# pr0board_main.net
KiCad netlist of a schematic drawn in EAGLE
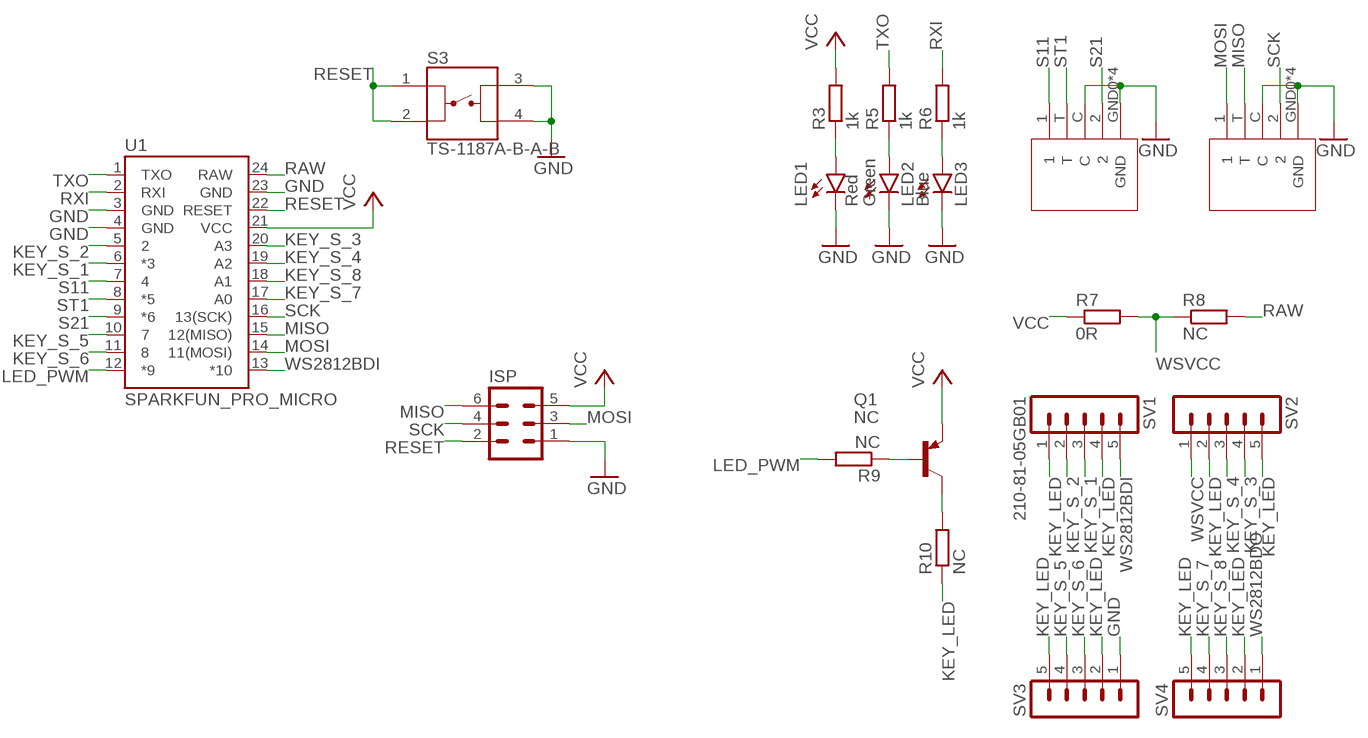
[diagram p0: schematic, sheet 1]

(export (version "E")
  (design (tool "Eeschema 10.0.6"))
  (components
    (comp (ref "ISP")
      (value "MA03-2")
      (footprint "eagle-import:MA03-2")
      (libsource (lib "eagle-import") (part "MA03-2"))
    )
    (comp (ref "LED1")
      (value "Red")
      (footprint "eagle-import:CHIP-LED0603")
      (libsource (lib "eagle-import") (part "LEDCHIP-LED0603"))
    )
    (comp (ref "LED2")
      (value "Green")
      (footprint "eagle-import:CHIP-LED0603")
      (libsource (lib "eagle-import") (part "LEDCHIP-LED0603"))
    )
    (comp (ref "LED3")
      (value "Blue")
      (footprint "eagle-import:CHIP-LED0603")
      (libsource (lib "eagle-import") (part "LEDCHIP-LED0603"))
    )
    (comp (ref "Q1")
      (value "NC")
      (footprint "eagle-import:SOT23")
      (libsource (lib "eagle-import") (part "-?SOT23MMBTA56"))
    )
    (comp (ref "R3")
      (value "1k")
      (footprint "eagle-import:R0603")
      (libsource (lib "eagle-import") (part "resistor_348_R-EU_R0603"))
    )
    (comp (ref "R5")
      (value "1k")
      (footprint "eagle-import:R0603")
      (libsource (lib "eagle-import") (part "resistor_348_R-EU_R0603"))
    )
    (comp (ref "R6")
      (value "1k")
      (footprint "eagle-import:R0603")
      (libsource (lib "eagle-import") (part "resistor_348_R-EU_R0603"))
    )
    (comp (ref "R7")
      (value "0R")
      (footprint "eagle-import:R0603")
      (libsource (lib "eagle-import") (part "resistor_348_R-EU_R0603"))
    )
    (comp (ref "R8")
      (value "NC")
      (footprint "eagle-import:R0603")
      (libsource (lib "eagle-import") (part "resistor_348_R-EU_R0603"))
    )
    (comp (ref "R9")
      (value "NC")
      (footprint "eagle-import:R0603")
      (libsource (lib "eagle-import") (part "R-EU_R0603"))
    )
    (comp (ref "R10")
      (value "NC")
      (footprint "eagle-import:R0805")
      (libsource (lib "eagle-import") (part "R-EU_R0805"))
    )
    (comp (ref "S1")
      (value "TM-2024A")
      (footprint "eagle-import:TM-2024A")
      (libsource (lib "eagle-import") (part "TM-2024A"))
    )
    (comp (ref "S2")
      (value "TM-2024A")
      (footprint "eagle-import:TM-2024A")
      (libsource (lib "eagle-import") (part "TM-2024A"))
    )
    (comp (ref "S3")
      (value "TS-1187A-B-A-B")
      (footprint "eagle-import:SW_PTS525SM15SMTR2LFS")
      (fields (field (name "MF") "C&K") (field (name "MP") "PTS525SM15SMTR2LFS"))
      (libsource (lib "eagle-import") (part "PTS525SM15SMTR2LFS"))
    )
    (comp (ref "SV1")
      (value "210-81-05GB01")
      (footprint "eagle-import:MA05-1")
      (libsource (lib "eagle-import") (part "MA05-1"))
    )
    (comp (ref "SV2")
      (value "MA05-1")
      (footprint "eagle-import:MA05-1")
      (libsource (lib "eagle-import") (part "MA05-1"))
    )
    (comp (ref "SV3")
      (value "MA05-1")
      (footprint "eagle-import:MA05-1")
      (libsource (lib "eagle-import") (part "MA05-1"))
    )
    (comp (ref "SV4")
      (value "MA05-1")
      (footprint "eagle-import:MA05-1")
      (libsource (lib "eagle-import") (part "MA05-1"))
    )
    (comp (ref "U1")
      (value "SPARKFUN_PRO_MICRO")
      (footprint "eagle-import:SPARKFUN_PRO_MICRO")
      (libsource (lib "eagle-import") (part "SPARKFUN_PRO_MICRO"))
    )
  )
  (nets
    (net (code "1") (name "/KEY_LED") (class "Default")
      (node (ref "R10") (pin "1") (pinfunction "1_1") (pintype "passive"))
      (node (ref "SV1") (pin "1") (pinfunction "1_1") (pintype "passive"))
      (node (ref "SV1") (pin "4") (pinfunction "4_4") (pintype "passive"))
      (node (ref "SV2") (pin "2") (pinfunction "2_2") (pintype "passive"))
      (node (ref "SV2") (pin "5") (pinfunction "5_5") (pintype "passive"))
      (node (ref "SV3") (pin "2") (pinfunction "2_2") (pintype "passive"))
      (node (ref "SV3") (pin "5") (pinfunction "5_5") (pintype "passive"))
      (node (ref "SV4") (pin "2") (pinfunction "2_2") (pintype "passive"))
      (node (ref "SV4") (pin "5") (pinfunction "5_5") (pintype "passive"))
    )
    (net (code "2") (name "/KEY_S_1") (class "Default")
      (node (ref "SV1") (pin "3") (pinfunction "3_3") (pintype "passive"))
      (node (ref "U1") (pin "6") (pinfunction "*3_6") (pintype "bidirectional"))
    )
    (net (code "3") (name "/KEY_S_2") (class "Default")
      (node (ref "SV1") (pin "2") (pinfunction "2_2") (pintype "passive"))
      (node (ref "U1") (pin "5") (pinfunction "2_5") (pintype "bidirectional"))
    )
    (net (code "4") (name "/KEY_S_3") (class "Default")
      (node (ref "SV2") (pin "4") (pinfunction "4_4") (pintype "passive"))
      (node (ref "U1") (pin "20") (pinfunction "A3_20") (pintype "bidirectional"))
    )
    (net (code "5") (name "/KEY_S_4") (class "Default")
      (node (ref "SV2") (pin "3") (pinfunction "3_3") (pintype "passive"))
      (node (ref "U1") (pin "19") (pinfunction "A2_19") (pintype "bidirectional"))
    )
    (net (code "6") (name "/KEY_S_5") (class "Default")
      (node (ref "SV3") (pin "4") (pinfunction "4_4") (pintype "passive"))
      (node (ref "U1") (pin "10") (pinfunction "7_10") (pintype "bidirectional"))
    )
    (net (code "7") (name "/KEY_S_6") (class "Default")
      (node (ref "SV3") (pin "3") (pinfunction "3_3") (pintype "passive"))
      (node (ref "U1") (pin "11") (pinfunction "8_11") (pintype "bidirectional"))
    )
    (net (code "8") (name "/KEY_S_7") (class "Default")
      (node (ref "SV4") (pin "4") (pinfunction "4_4") (pintype "passive"))
      (node (ref "U1") (pin "17") (pinfunction "A0_17") (pintype "bidirectional"))
    )
    (net (code "9") (name "/KEY_S_8") (class "Default")
      (node (ref "SV4") (pin "3") (pinfunction "3_3") (pintype "passive"))
      (node (ref "U1") (pin "18") (pinfunction "A1_18") (pintype "bidirectional"))
    )
    (net (code "10") (name "/LED_PWM") (class "Default")
      (node (ref "R9") (pin "2") (pinfunction "2_2") (pintype "passive"))
      (node (ref "U1") (pin "12") (pinfunction "*9_12") (pintype "bidirectional"))
    )
    (net (code "11") (name "/MISO") (class "Default")
      (node (ref "ISP") (pin "6") (pinfunction "6_6") (pintype "passive"))
      (node (ref "S2") (pin "T") (pinfunction "T_T") (pintype "bidirectional"))
      (node (ref "U1") (pin "15") (pinfunction "12(MISO)_15") (pintype "bidirectional"))
    )
    (net (code "12") (name "/MOSI") (class "Default")
      (node (ref "ISP") (pin "3") (pinfunction "3_3") (pintype "passive"))
      (node (ref "S2") (pin "1") (pinfunction "1_1") (pintype "bidirectional"))
      (node (ref "U1") (pin "14") (pinfunction "11(MOSI)_14") (pintype "bidirectional"))
    )
    (net (code "13") (name "/RAW") (class "Default")
      (node (ref "R8") (pin "2") (pinfunction "2_2") (pintype "passive"))
      (node (ref "U1") (pin "24") (pinfunction "RAW_24") (pintype "power_in"))
    )
    (net (code "14") (name "/RESET") (class "Default")
      (node (ref "ISP") (pin "2") (pinfunction "2_2") (pintype "passive"))
      (node (ref "S3") (pin "1") (pinfunction "1_1") (pintype "passive"))
      (node (ref "S3") (pin "2") (pinfunction "2_2") (pintype "passive"))
      (node (ref "U1") (pin "22") (pinfunction "RESET_22") (pintype "bidirectional"))
    )
    (net (code "15") (name "/RXI") (class "Default")
      (node (ref "R6") (pin "2") (pinfunction "2_2") (pintype "passive"))
      (node (ref "U1") (pin "2") (pinfunction "RXI_2") (pintype "bidirectional"))
    )
    (net (code "16") (name "/S11") (class "Default")
      (node (ref "S1") (pin "1") (pinfunction "1_1") (pintype "bidirectional"))
      (node (ref "U1") (pin "7") (pinfunction "4_7") (pintype "bidirectional"))
    )
    (net (code "17") (name "/S21") (class "Default")
      (node (ref "S1") (pin "2") (pinfunction "2_2") (pintype "bidirectional"))
      (node (ref "U1") (pin "9") (pinfunction "*6_9") (pintype "bidirectional"))
    )
    (net (code "18") (name "/SCK") (class "Default")
      (node (ref "ISP") (pin "4") (pinfunction "4_4") (pintype "passive"))
      (node (ref "S2") (pin "2") (pinfunction "2_2") (pintype "bidirectional"))
      (node (ref "U1") (pin "16") (pinfunction "13(SCK)_16") (pintype "bidirectional"))
    )
    (net (code "19") (name "/ST1") (class "Default")
      (node (ref "S1") (pin "T") (pinfunction "T_T") (pintype "bidirectional"))
      (node (ref "U1") (pin "8") (pinfunction "*5_8") (pintype "bidirectional"))
    )
    (net (code "20") (name "/TXO") (class "Default")
      (node (ref "R5") (pin "2") (pinfunction "2_2") (pintype "passive"))
      (node (ref "U1") (pin "1") (pinfunction "TXO_1") (pintype "bidirectional"))
    )
    (net (code "21") (name "/WS2812BDI") (class "Default")
      (node (ref "SV1") (pin "5") (pinfunction "5_5") (pintype "passive"))
      (node (ref "U1") (pin "13") (pinfunction "*10_13") (pintype "bidirectional"))
    )
    (net (code "22") (name "/WS2812BDO") (class "Default")
      (node (ref "SV4") (pin "1") (pinfunction "1_1") (pintype "passive"))
    )
    (net (code "23") (name "/WSVCC") (class "Default")
      (node (ref "R7") (pin "2") (pinfunction "2_2") (pintype "passive"))
      (node (ref "R8") (pin "1") (pinfunction "1_1") (pintype "passive"))
      (node (ref "SV2") (pin "1") (pinfunction "1_1") (pintype "passive"))
    )
    (net (code "24") (name "GND") (class "Default")
      (node (ref "ISP") (pin "1") (pinfunction "1_1") (pintype "passive"))
      (node (ref "LED1") (pin "C") (pinfunction "C_C") (pintype "passive"))
      (node (ref "LED2") (pin "C") (pinfunction "C_C") (pintype "passive"))
      (node (ref "LED3") (pin "C") (pinfunction "C_C") (pintype "passive"))
      (node (ref "S1") (pin "C") (pinfunction "C_C") (pintype "bidirectional"))
      (node (ref "S1") (pin "GND0") (pinfunction "GND_GND0") (pintype "bidirectional"))
      (node (ref "S1") (pin "GND1") (pinfunction "GND_GND1") (pintype "bidirectional"))
      (node (ref "S1") (pin "GND2") (pinfunction "GND_GND2") (pintype "bidirectional"))
      (node (ref "S1") (pin "GND3") (pinfunction "GND_GND3") (pintype "bidirectional"))
      (node (ref "S2") (pin "C") (pinfunction "C_C") (pintype "bidirectional"))
      (node (ref "S2") (pin "GND0") (pinfunction "GND_GND0") (pintype "bidirectional"))
      (node (ref "S2") (pin "GND1") (pinfunction "GND_GND1") (pintype "bidirectional"))
      (node (ref "S2") (pin "GND2") (pinfunction "GND_GND2") (pintype "bidirectional"))
      (node (ref "S2") (pin "GND3") (pinfunction "GND_GND3") (pintype "bidirectional"))
      (node (ref "S3") (pin "3") (pinfunction "3_3") (pintype "passive"))
      (node (ref "S3") (pin "4") (pinfunction "4_4") (pintype "passive"))
      (node (ref "SV3") (pin "1") (pinfunction "1_1") (pintype "passive"))
      (node (ref "U1") (pin "23") (pinfunction "GND_23") (pintype "power_in"))
      (node (ref "U1") (pin "3") (pinfunction "GND_3") (pintype "power_in"))
      (node (ref "U1") (pin "4") (pinfunction "GND_4") (pintype "power_in"))
    )
    (net (code "25") (name "Net-(LED1-PadA)") (class "Default")
      (node (ref "LED1") (pin "A") (pinfunction "A_A") (pintype "passive"))
      (node (ref "R3") (pin "1") (pinfunction "1_1") (pintype "passive"))
    )
    (net (code "26") (name "Net-(LED2-PadA)") (class "Default")
      (node (ref "LED2") (pin "A") (pinfunction "A_A") (pintype "passive"))
      (node (ref "R5") (pin "1") (pinfunction "1_1") (pintype "passive"))
    )
    (net (code "27") (name "Net-(LED3-PadA)") (class "Default")
      (node (ref "LED3") (pin "A") (pinfunction "A_A") (pintype "passive"))
      (node (ref "R6") (pin "1") (pinfunction "1_1") (pintype "passive"))
    )
    (net (code "28") (name "Net-(Q1-B)") (class "Default")
      (node (ref "Q1") (pin "1") (pinfunction "B_1") (pintype "passive"))
      (node (ref "R9") (pin "1") (pinfunction "1_1") (pintype "passive"))
    )
    (net (code "29") (name "Net-(Q1-C)") (class "Default")
      (node (ref "Q1") (pin "3") (pinfunction "C_3") (pintype "passive"))
      (node (ref "R10") (pin "2") (pinfunction "2_2") (pintype "passive"))
    )
    (net (code "30") (name "VCC") (class "Default")
      (node (ref "ISP") (pin "5") (pinfunction "5_5") (pintype "passive"))
      (node (ref "Q1") (pin "2") (pinfunction "E_2") (pintype "passive"))
      (node (ref "R3") (pin "2") (pinfunction "2_2") (pintype "passive"))
      (node (ref "R7") (pin "1") (pinfunction "1_1") (pintype "passive"))
      (node (ref "U1") (pin "21") (pinfunction "VCC_21") (pintype "power_in"))
    )
  )
)
